# 454_mic.net
KiCad netlist of a schematic drawn in EAGLE
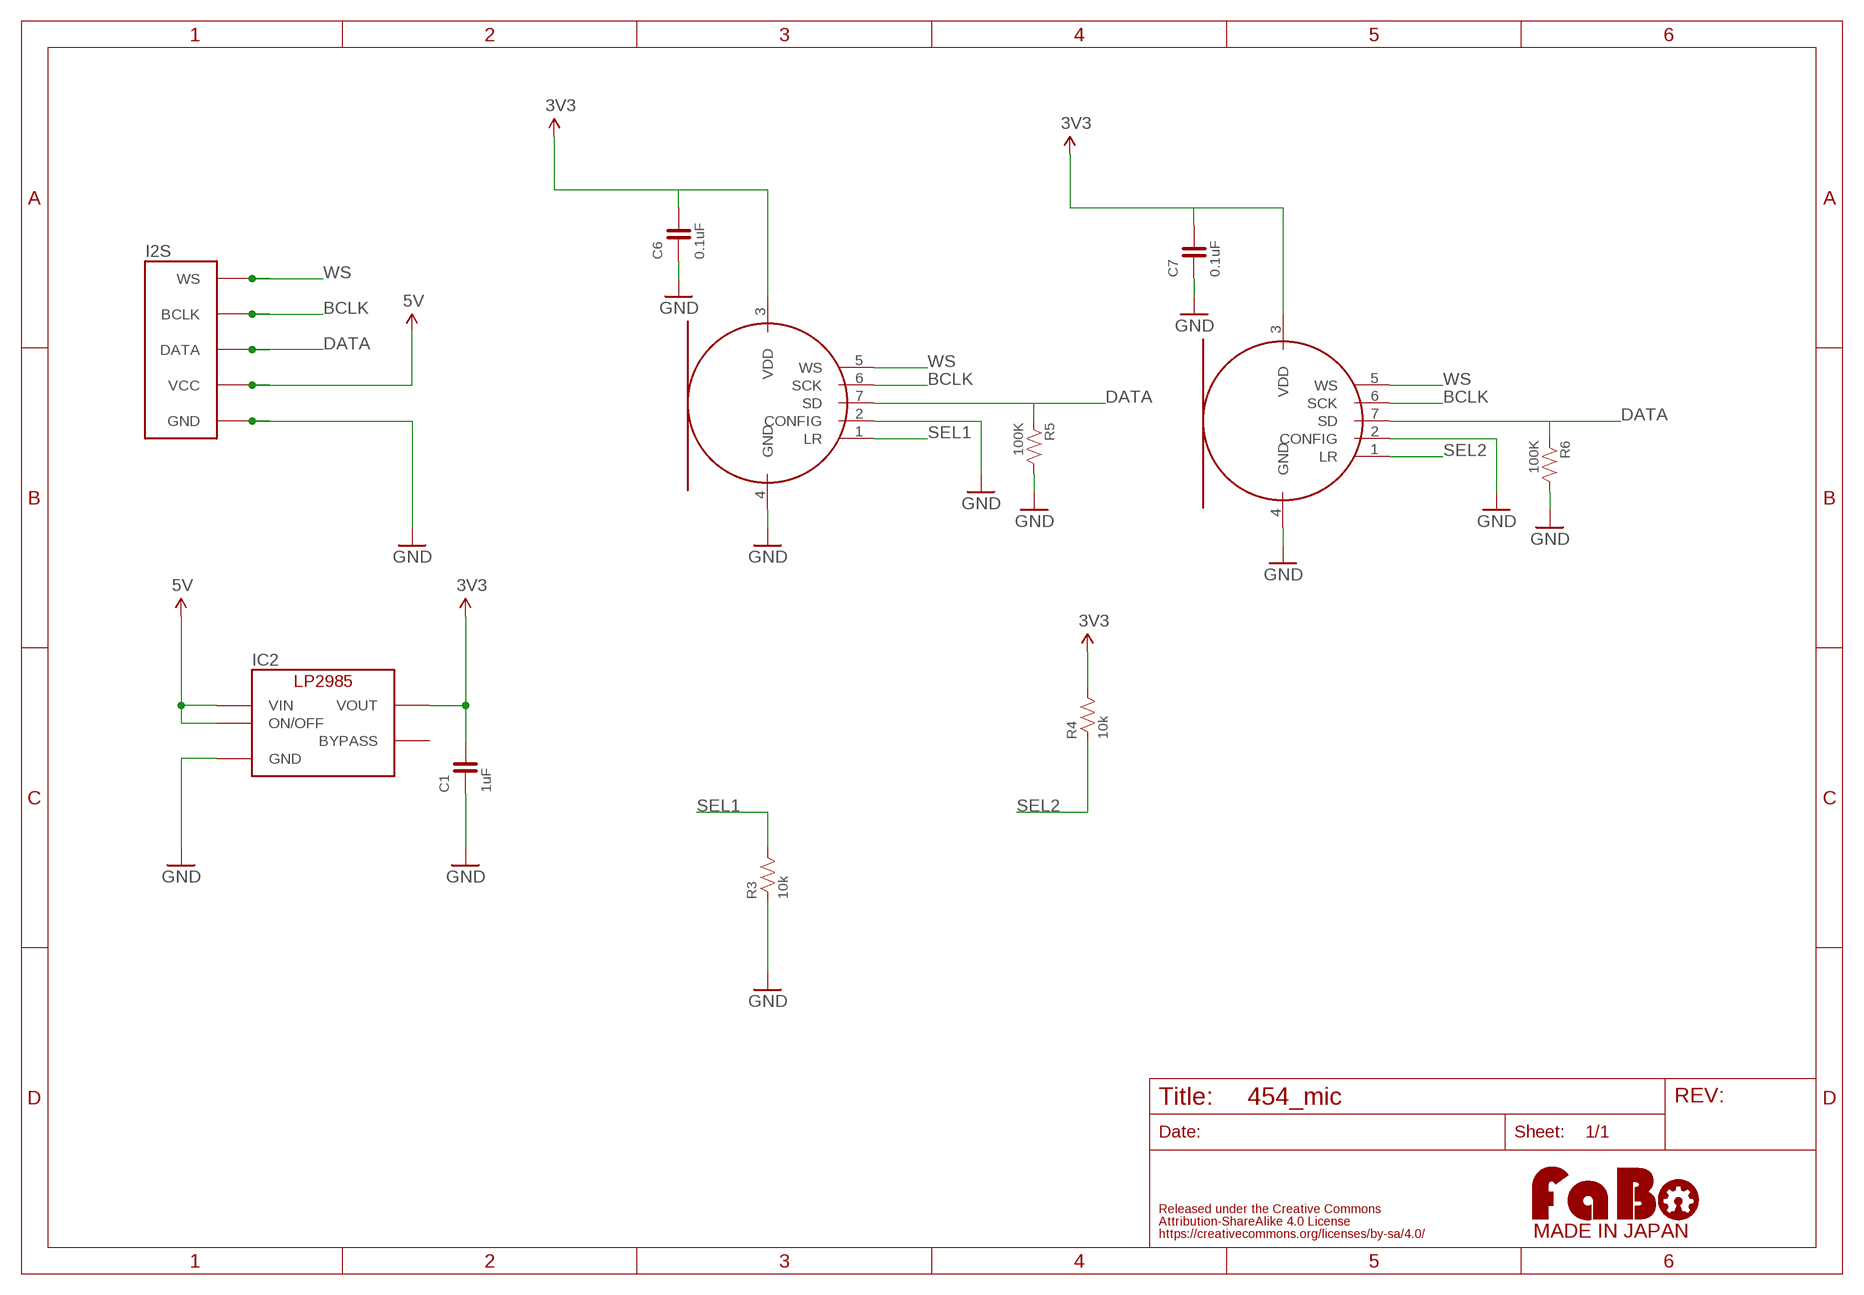
[diagram p0: schematic, sheet 1]

(export (version "E")
  (design (tool "Eeschema 10.0.6"))
  (components
    (comp (ref "C1")
      (value "1uF")
      (footprint "eagle-import:0603")
      (libsource (lib "eagle-import") (part "CAPACITOR-0603"))
    )
    (comp (ref "C6")
      (value "0.1uF")
      (footprint "eagle-import:0603")
      (libsource (lib "eagle-import") (part "CAPACITOR-0603"))
    )
    (comp (ref "C7")
      (value "0.1uF")
      (footprint "eagle-import:0603")
      (libsource (lib "eagle-import") (part "CAPACITOR-0603"))
    )
    (comp (ref "I2S")
      (value "FABO_BRICK_I2SLONG")
      (footprint "eagle-import:FABO_BRICK_I2S_S05B-PASK-2_LONG")
      (libsource (lib "eagle-import") (part "FABO_BRICK_I2SLONG"))
    )
    (comp (ref "IC2")
      (value "LP2985-33DBV")
      (footprint "eagle-import:SOT-23-5")
      (libsource (lib "eagle-import") (part "LP2985-33DBV"))
    )
    (comp (ref "MIC_LEFT")
      (value "TDK-ICS43432")
      (footprint "eagle-import:TDK-ICS43432")
      (libsource (lib "eagle-import") (part "TDK-ICS43432"))
    )
    (comp (ref "MIC_RIGHT")
      (value "TDK-ICS43432")
      (footprint "eagle-import:TDK-ICS43432")
      (libsource (lib "eagle-import") (part "TDK-ICS43432"))
    )
    (comp (ref "R3")
      (value "10k")
      (footprint "eagle-import:0603")
      (libsource (lib "eagle-import") (part "RESISTOR-0603"))
    )
    (comp (ref "R4")
      (value "10k")
      (footprint "eagle-import:0603")
      (libsource (lib "eagle-import") (part "RESISTOR-0603"))
    )
    (comp (ref "R5")
      (value "100K")
      (footprint "eagle-import:0603")
      (libsource (lib "eagle-import") (part "RESISTOR-0603"))
    )
    (comp (ref "R6")
      (value "100K")
      (footprint "eagle-import:0603")
      (libsource (lib "eagle-import") (part "RESISTOR-0603"))
    )
    (comp (ref "U$3")
      (value "LOGO_FABO-M_BOTTOM")
      (footprint "eagle-import:LOGO_FABO_MS_BOTTOM")
      (libsource (lib "eagle-import") (part "LOGO_FABO-M_BOTTOM"))
    )
  )
  (nets
    (net (code "1") (name "/BCLK") (class "Default")
      (node (ref "I2S") (pin "BCLK") (pinfunction "BCLK_BCLK") (pintype "bidirectional"))
      (node (ref "MIC_LEFT") (pin "6") (pinfunction "SCK_6") (pintype "bidirectional"))
      (node (ref "MIC_RIGHT") (pin "6") (pinfunction "SCK_6") (pintype "bidirectional"))
    )
    (net (code "2") (name "/DATA") (class "Default")
      (node (ref "I2S") (pin "DATA") (pinfunction "DATA_DATA") (pintype "bidirectional"))
      (node (ref "MIC_LEFT") (pin "7") (pinfunction "SD_7") (pintype "bidirectional"))
      (node (ref "MIC_RIGHT") (pin "7") (pinfunction "SD_7") (pintype "bidirectional"))
      (node (ref "R5") (pin "1") (pinfunction "1_1") (pintype "bidirectional"))
      (node (ref "R6") (pin "1") (pinfunction "1_1") (pintype "bidirectional"))
    )
    (net (code "3") (name "/SEL1") (class "Default")
      (node (ref "MIC_LEFT") (pin "1") (pinfunction "LR_1") (pintype "bidirectional"))
      (node (ref "R3") (pin "2") (pinfunction "2_2") (pintype "bidirectional"))
    )
    (net (code "4") (name "/SEL2") (class "Default")
      (node (ref "MIC_RIGHT") (pin "1") (pinfunction "LR_1") (pintype "bidirectional"))
      (node (ref "R4") (pin "1") (pinfunction "1_1") (pintype "bidirectional"))
    )
    (net (code "5") (name "/WS") (class "Default")
      (node (ref "I2S") (pin "WS") (pinfunction "WS_WS") (pintype "bidirectional"))
      (node (ref "MIC_LEFT") (pin "5") (pinfunction "WS_5") (pintype "bidirectional"))
      (node (ref "MIC_RIGHT") (pin "5") (pinfunction "WS_5") (pintype "bidirectional"))
    )
    (net (code "6") (name "3V3") (class "Default")
      (node (ref "C1") (pin "2") (pinfunction "2_2") (pintype "passive"))
      (node (ref "C6") (pin "2") (pinfunction "2_2") (pintype "passive"))
      (node (ref "C7") (pin "2") (pinfunction "2_2") (pintype "passive"))
      (node (ref "IC2") (pin "5") (pinfunction "VOUT_5") (pintype "output"))
      (node (ref "MIC_LEFT") (pin "3") (pinfunction "VDD_3") (pintype "bidirectional"))
      (node (ref "MIC_RIGHT") (pin "3") (pinfunction "VDD_3") (pintype "bidirectional"))
      (node (ref "R4") (pin "2") (pinfunction "2_2") (pintype "bidirectional"))
    )
    (net (code "7") (name "5V") (class "Default")
      (node (ref "I2S") (pin "VCC") (pinfunction "VCC_VCC") (pintype "bidirectional"))
      (node (ref "IC2") (pin "1") (pinfunction "VIN_1") (pintype "input"))
      (node (ref "IC2") (pin "3") (pinfunction "ON/OFF_3") (pintype "input"))
    )
    (net (code "8") (name "GND") (class "Default")
      (node (ref "C1") (pin "1") (pinfunction "1_1") (pintype "passive"))
      (node (ref "C6") (pin "1") (pinfunction "1_1") (pintype "passive"))
      (node (ref "C7") (pin "1") (pinfunction "1_1") (pintype "passive"))
      (node (ref "I2S") (pin "GND") (pinfunction "GND_GND") (pintype "bidirectional"))
      (node (ref "IC2") (pin "2") (pinfunction "GND_2") (pintype "power_in"))
      (node (ref "MIC_LEFT") (pin "2") (pinfunction "CONFIG_2") (pintype "bidirectional"))
      (node (ref "MIC_LEFT") (pin "4") (pinfunction "GND_4") (pintype "bidirectional"))
      (node (ref "MIC_RIGHT") (pin "2") (pinfunction "CONFIG_2") (pintype "bidirectional"))
      (node (ref "MIC_RIGHT") (pin "4") (pinfunction "GND_4") (pintype "bidirectional"))
      (node (ref "R3") (pin "1") (pinfunction "1_1") (pintype "bidirectional"))
      (node (ref "R5") (pin "2") (pinfunction "2_2") (pintype "bidirectional"))
      (node (ref "R6") (pin "2") (pinfunction "2_2") (pintype "bidirectional"))
    )
    (net (code "9") (name "unconnected-(IC2-BYPASS-Pad4)") (class "Default")
      (node (ref "IC2") (pin "4") (pinfunction "BYPASS_4") (pintype "bidirectional"))
    )
  )
)
